# 505147_1_1.net
KiCad netlist of a schematic drawn in Altium Designer
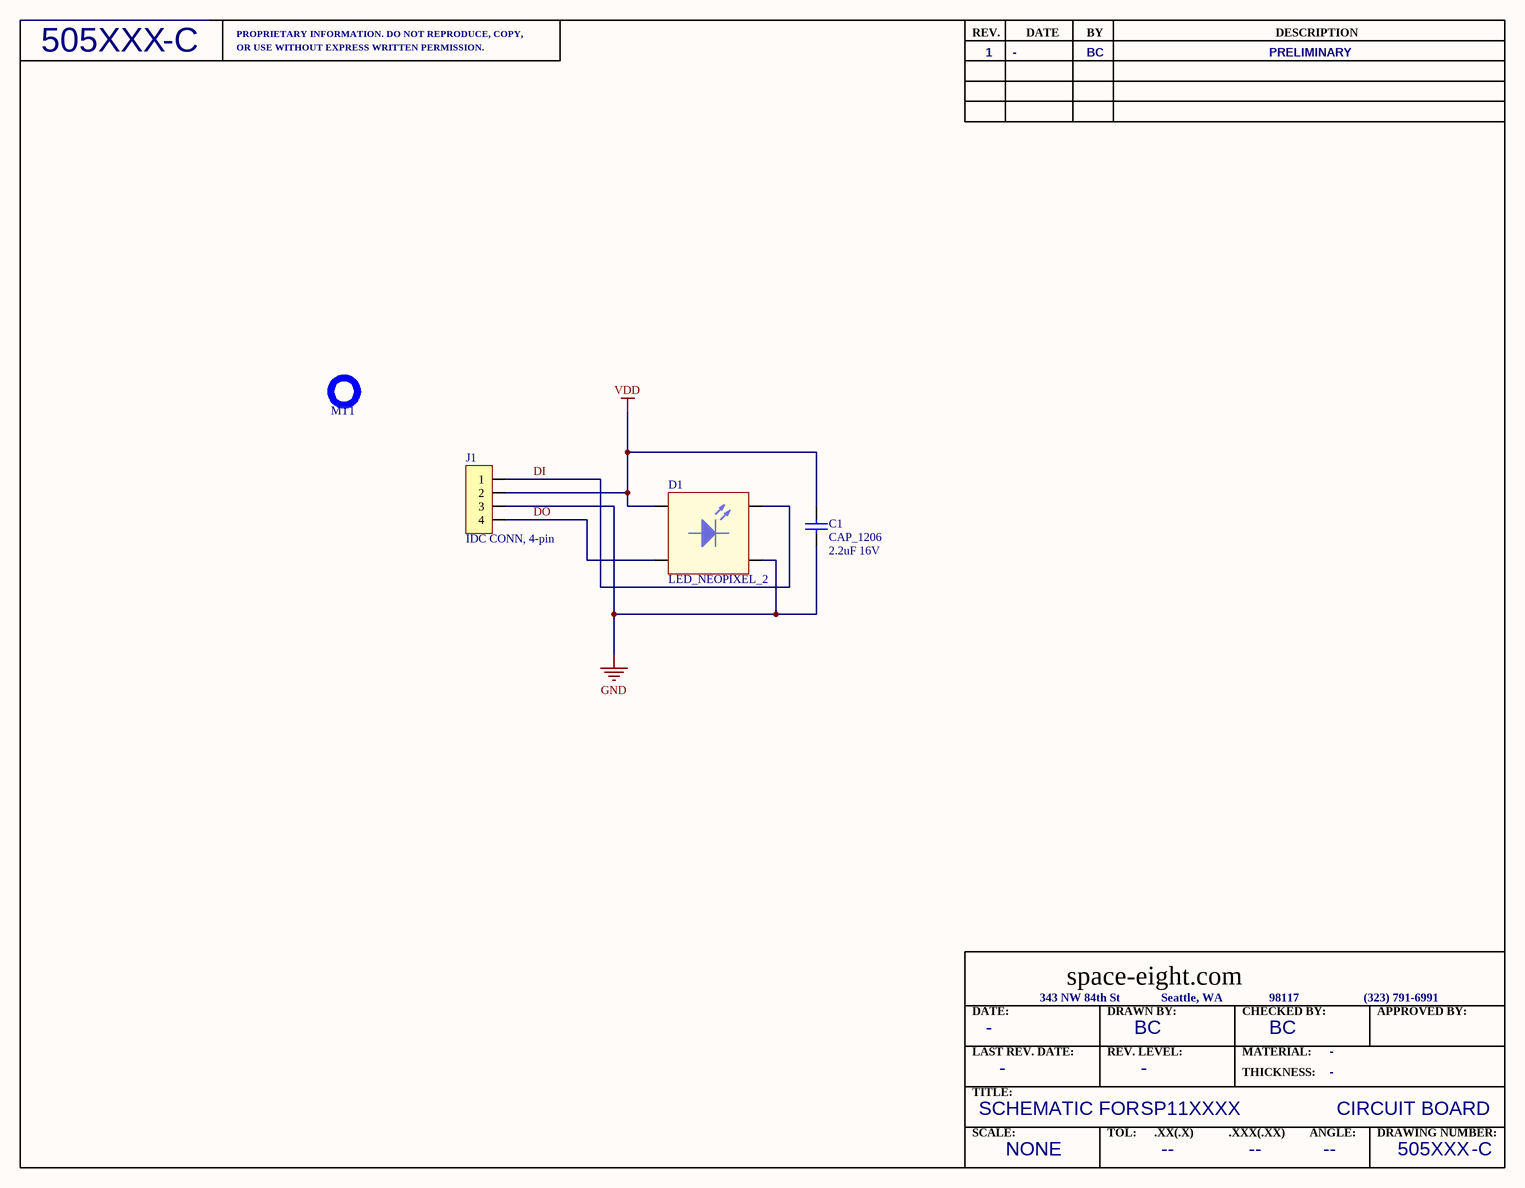
[diagram p0: 505147_1_1.SchDoc]

(export (version "E")
  (design (tool "Eeschema 10.0.6"))
  (components
    (comp (ref "C1")
      (value "CAP_1206")
      (footprint "SMT_1206_MOD")
      (description "CAP")
      (fields
        (field (name "MANUFACTURER") "Generic Components")
        (field (name "ALTIUM_VALUE") "2.2uF 16V")
        (field (name "PUBLISHER") "Altium Limited")
      )
      (libsource (lib "Custom_Lib_2") (part "CAP_1206"))
    )
    (comp (ref "D1")
      (value "LED_NEOPIXEL_2")
      (footprint "NEOPIXEL_2")
      (description "RGB NEOPIXEL")
      (fields (field (name "MANUFACTURER") "Generic Components") (field (name "PUBLISHER") "Altium Limited"))
      (libsource (lib "Custom_Lib_2") (part "LED_NEOPIXEL_2"))
    )
    (comp (ref "J1")
      (value "IDC CONN, 4-pin")
      (footprint "IDC_CONN_SMT_4-PIN")
      (description "ICD Connector, 4-Pin")
      (fields (field (name "PUBLISHER") "Altium Limited"))
      (libsource (lib "Custom_Lib_2") (part "IDC CONN, 4-pin"))
    )
    (comp (ref "MT1")
      (value "MOUNTING HOLE")
      (footprint "MOUNTING HOLE")
      (libsource (lib "Custom_Lib_2") (part "MOUNTING HOLE"))
    )
  )
  (nets
    (net (code "1") (name "/DI") (class "Default")
      (node (ref "D1") (pin "2") (pinfunction "DI_2") (pintype "passive"))
      (node (ref "J1") (pin "1") (pinfunction "1_1") (pintype "passive"))
    )
    (net (code "2") (name "/DO") (class "Default")
      (node (ref "D1") (pin "4") (pinfunction "DO_4") (pintype "passive"))
      (node (ref "J1") (pin "4") (pinfunction "4_4") (pintype "passive"))
    )
    (net (code "3") (name "GND") (class "Default")
      (node (ref "C1") (pin "1") (pinfunction "1_1") (pintype "passive"))
      (node (ref "D1") (pin "1") (pinfunction "GND_1") (pintype "passive"))
      (node (ref "J1") (pin "3") (pinfunction "3_3") (pintype "passive"))
    )
    (net (code "4") (name "VDD") (class "Default")
      (node (ref "C1") (pin "2") (pinfunction "2_2") (pintype "passive"))
      (node (ref "D1") (pin "3") (pinfunction "VDD_3") (pintype "passive"))
      (node (ref "J1") (pin "2") (pinfunction "2_2") (pintype "passive"))
    )
  )
)
